# battery_monitor_6803-2_Rev5.net
KiCad netlist of a schematic drawn in EAGLE
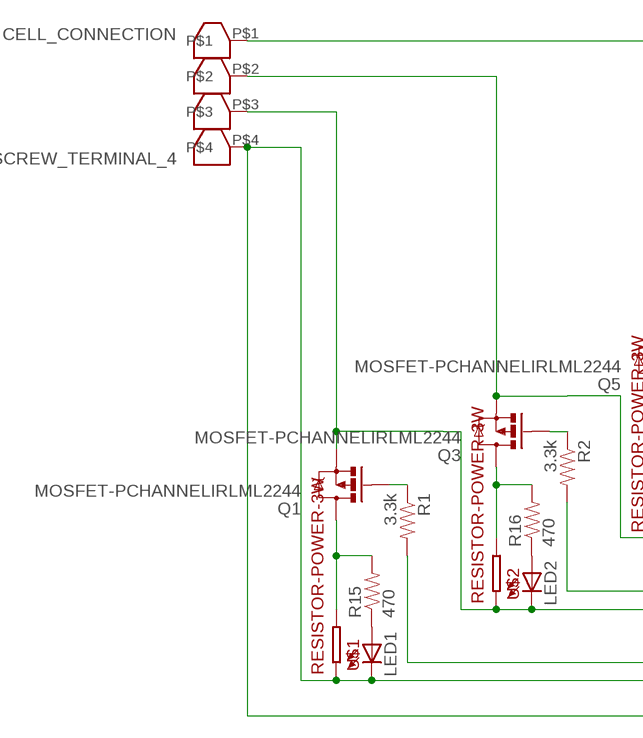
[diagram p0: schematic, sheet 1, part 1 of 2]
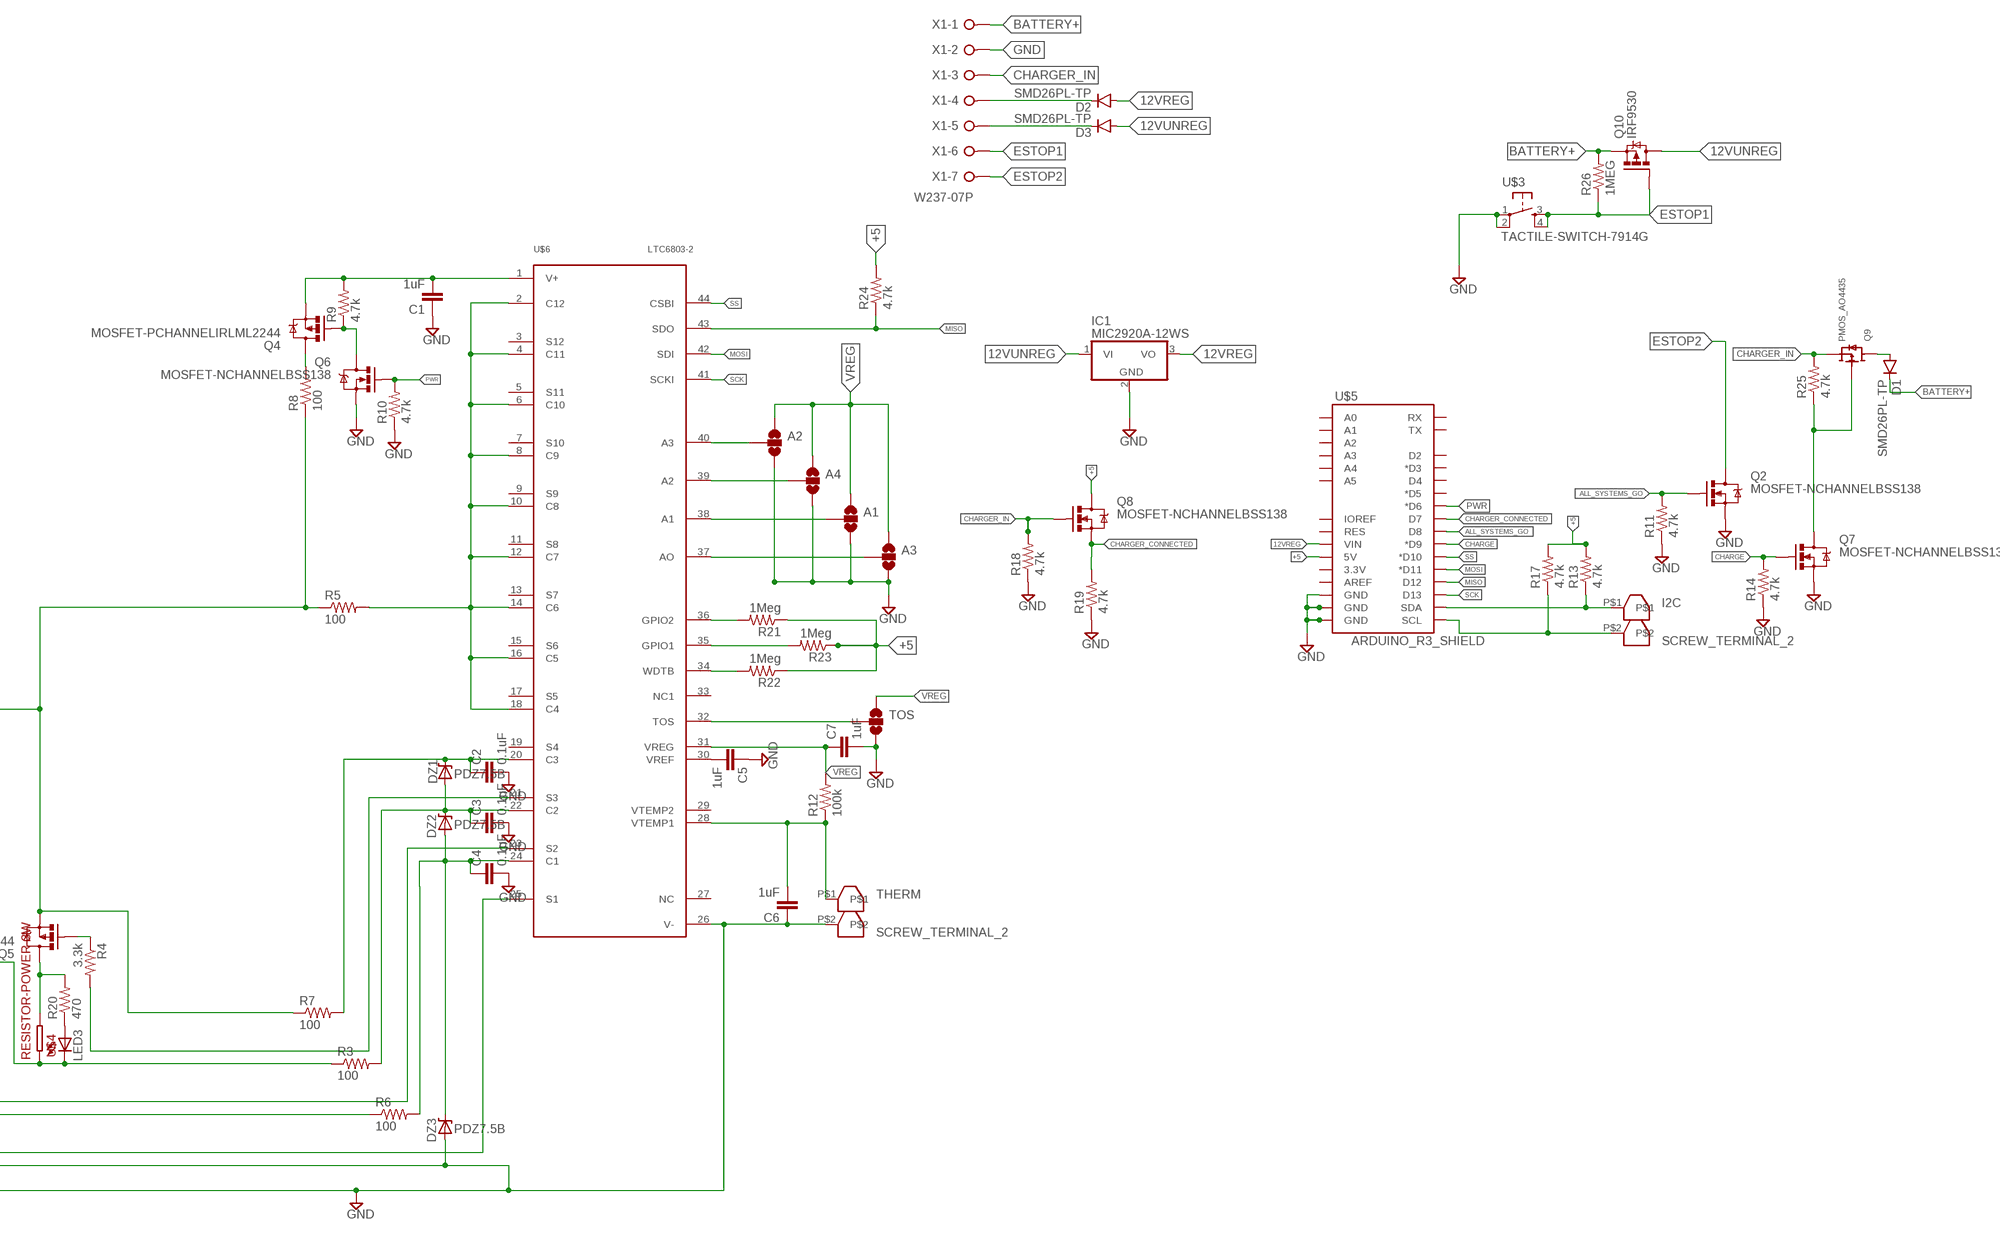
[diagram p1: schematic, sheet 1, part 2 of 2]

(export (version "E")
  (design (tool "Eeschema 10.0.6"))
  (components
    (comp (ref "A1")
      (value "SOLDERJUMPER_2WAYS")
      (footprint "eagle-import:SJ_3")
      (libsource (lib "eagle-import") (part "SOLDERJUMPER_2WAYS"))
    )
    (comp (ref "A2")
      (value "SOLDERJUMPER_2WAYS")
      (footprint "eagle-import:SJ_3")
      (libsource (lib "eagle-import") (part "SOLDERJUMPER_2WAYS"))
    )
    (comp (ref "A3")
      (value "SOLDERJUMPER_2WAYS")
      (footprint "eagle-import:SJ_3")
      (libsource (lib "eagle-import") (part "SOLDERJUMPER_2WAYS"))
    )
    (comp (ref "A4")
      (value "SOLDERJUMPER_2WAYS")
      (footprint "eagle-import:SJ_3")
      (libsource (lib "eagle-import") (part "SOLDERJUMPER_2WAYS"))
    )
    (comp (ref "C1")
      (value "1uF")
      (footprint "eagle-import:0603-CAP")
      (fields (field (name "MPN") "C0603X5R0J105M030BC") (field (name "PROD_ID") "CAP-08390"))
      (libsource (lib "eagle-import") (part "0.1UF-100V-10%(0603)"))
    )
    (comp (ref "C2")
      (value "0.1uF")
      (footprint "eagle-import:0603-CAP")
      (fields (field (name "MF") "AVX CORPORATION") (field (name "MPN") "0603YG104ZAT2A"))
      (libsource (lib "eagle-import") (part "0.1UF-100V-10%(0603)"))
    )
    (comp (ref "C3")
      (value "0.1uF")
      (footprint "eagle-import:0603-CAP")
      (fields (field (name "MF") "AVX CORPORATION") (field (name "MPN") "0603YG104ZAT2A"))
      (libsource (lib "eagle-import") (part "0.1UF-100V-10%(0603)"))
    )
    (comp (ref "C4")
      (value "0.1uF")
      (footprint "eagle-import:0603-CAP")
      (fields (field (name "MF") "AVX CORPORATION") (field (name "MPN") "0603YG104ZAT2A"))
      (libsource (lib "eagle-import") (part "0.1UF-100V-10%(0603)"))
    )
    (comp (ref "C5")
      (value "1uF")
      (footprint "eagle-import:0603-CAP")
      (fields (field (name "MPN") "C0603X5R0J105M030BC") (field (name "PROD_ID") "CAP-08390"))
      (libsource (lib "eagle-import") (part "0.1UF-100V-10%(0603)"))
    )
    (comp (ref "C6")
      (value "1uF")
      (footprint "eagle-import:0603-CAP")
      (fields (field (name "MPN") "C0603X5R0J105M030BC") (field (name "PROD_ID") "CAP-08390"))
      (libsource (lib "eagle-import") (part "0.1UF-100V-10%(0603)"))
    )
    (comp (ref "C7")
      (value "1uF")
      (footprint "eagle-import:0603-CAP")
      (fields (field (name "MPN") "C0603X5R0J105M030BC") (field (name "PROD_ID") "CAP-08390"))
      (libsource (lib "eagle-import") (part "0.1UF-100V-10%(0603)"))
    )
    (comp (ref "CELL_CONNECTION")
      (value "SCREW_TERMINAL_4")
      (footprint "eagle-import:SCREW_TERMINAL_4")
      (fields (field (name "MF") "TYCO ELECTRONICS") (field (name "MPN") "282834-4"))
      (libsource (lib "eagle-import") (part "SCREW_TERMINAL_4"))
    )
    (comp (ref "D1")
      (value "SMD26PL-TP")
      (footprint "eagle-import:SOD-123")
      (libsource (lib "eagle-import") (part "DIODESOD123"))
    )
    (comp (ref "D2")
      (value "SMD26PL-TP")
      (footprint "eagle-import:SOD-123")
      (libsource (lib "eagle-import") (part "DIODESOD123"))
    )
    (comp (ref "D3")
      (value "SMD26PL-TP")
      (footprint "eagle-import:SOD-123")
      (libsource (lib "eagle-import") (part "DIODESOD123"))
    )
    (comp (ref "DZ1")
      (value "PDZ7.5B")
      (footprint "eagle-import:SOD-323@1")
      (fields (field (name "MPN") "PDZ7.5B,115"))
      (libsource (lib "eagle-import") (part "DIODE-ZENER-BZT52"))
    )
    (comp (ref "DZ2")
      (value "PDZ7.5B")
      (footprint "eagle-import:SOD-323@1")
      (fields (field (name "MPN") "PDZ7.5B,115"))
      (libsource (lib "eagle-import") (part "DIODE-ZENER-BZT52"))
    )
    (comp (ref "DZ3")
      (value "PDZ7.5B")
      (footprint "eagle-import:SOD-323@1")
      (fields (field (name "MPN") "PDZ7.5B,115"))
      (libsource (lib "eagle-import") (part "DIODE-ZENER-BZT52"))
    )
    (comp (ref "I2C")
      (value "SCREW_TERMINAL_2")
      (footprint "eagle-import:SCREW_TERMINAL_2")
      (fields (field (name "MF") "TYCO ELECTRONICS") (field (name "MPN") "282834-2"))
      (libsource (lib "eagle-import") (part "SCREW_TERMINAL_2"))
    )
    (comp (ref "IC1")
      (value "MIC2920A-12WS")
      (footprint "eagle-import:SOT223")
      (libsource (lib "eagle-import") (part "MCP1703DB"))
    )
    (comp (ref "LED1")
      (value "LED0603")
      (footprint "eagle-import:LED-0603")
      (fields (field (name "MPN") "150060RS75000"))
      (libsource (lib "eagle-import") (part "LED0603"))
    )
    (comp (ref "LED2")
      (value "LED0603")
      (footprint "eagle-import:LED-0603")
      (fields (field (name "MPN") "150060RS75000"))
      (libsource (lib "eagle-import") (part "LED0603"))
    )
    (comp (ref "LED3")
      (value "LED0603")
      (footprint "eagle-import:LED-0603")
      (fields (field (name "MPN") "150060RS75000"))
      (libsource (lib "eagle-import") (part "LED0603"))
    )
    (comp (ref "Q1")
      (value "MOSFET-PCHANNELIRLML2244")
      (footprint "eagle-import:SOT23-3@1")
      (fields (field (name "MPN") "SI2369DS-T1-GE3"))
      (libsource (lib "eagle-import") (part "MOSFET-PCHANNELIRLML2244"))
    )
    (comp (ref "Q2")
      (value "MOSFET-NCHANNELBSS138")
      (footprint "eagle-import:SOT23")
      (fields (field (name "MPN") "IRLML0030TRPBF"))
      (libsource (lib "eagle-import") (part "MOSFET-NCHANNELBSS138"))
    )
    (comp (ref "Q3")
      (value "MOSFET-PCHANNELIRLML2244")
      (footprint "eagle-import:SOT23-3@1")
      (fields (field (name "MPN") "SI2369DS-T1-GE3"))
      (libsource (lib "eagle-import") (part "MOSFET-PCHANNELIRLML2244"))
    )
    (comp (ref "Q4")
      (value "MOSFET-PCHANNELIRLML2244")
      (footprint "eagle-import:SOT23-3@1")
      (fields (field (name "MPN") "SI2369DS-T1-GE3"))
      (libsource (lib "eagle-import") (part "MOSFET-PCHANNELIRLML2244"))
    )
    (comp (ref "Q5")
      (value "MOSFET-PCHANNELIRLML2244")
      (footprint "eagle-import:SOT23-3@1")
      (fields (field (name "MPN") "SI2369DS-T1-GE3"))
      (libsource (lib "eagle-import") (part "MOSFET-PCHANNELIRLML2244"))
    )
    (comp (ref "Q6")
      (value "MOSFET-NCHANNELBSS138")
      (footprint "eagle-import:SOT23")
      (fields (field (name "MPN") "IRLML0030TRPBF"))
      (libsource (lib "eagle-import") (part "MOSFET-NCHANNELBSS138"))
    )
    (comp (ref "Q7")
      (value "MOSFET-NCHANNELBSS138")
      (footprint "eagle-import:SOT23")
      (fields (field (name "MPN") "IRLML0030TRPBF"))
      (libsource (lib "eagle-import") (part "MOSFET-NCHANNELBSS138"))
    )
    (comp (ref "Q8")
      (value "MOSFET-NCHANNELBSS138")
      (footprint "eagle-import:SOT23")
      (fields (field (name "MPN") "IRLML0030TRPBF") (field (name "PROD_ID") "TRANS-00830"))
      (libsource (lib "eagle-import") (part "MOSFET-NCHANNELBSS138"))
    )
    (comp (ref "Q9")
      (value "PMOS_AO4435")
      (footprint "eagle-import:SOIC8")
      (fields (field (name "MPN") "SI9407BDY-T1-GE3"))
      (libsource (lib "eagle-import") (part "PMOS_AO4435"))
    )
    (comp (ref "Q10")
      (value "IRF9530")
      (footprint "eagle-import:TO220BV")
      (fields (field (name "MPN") "NTE2383"))
      (libsource (lib "eagle-import") (part "IRF9530"))
    )
    (comp (ref "R1")
      (value "3.3k")
      (footprint "eagle-import:0603-RES")
      (fields (field (name "MF") "VISHAY/DALE") (field (name "MPN") "CRCW06033K00FKEA"))
      (libsource (lib "eagle-import") (part "3.3KOHM1/10W1%(0603)"))
    )
    (comp (ref "R2")
      (value "3.3k")
      (footprint "eagle-import:0603-RES")
      (fields (field (name "MF") "VISHAY/DALE") (field (name "MPN") "CRCW06033K00FKEA"))
      (libsource (lib "eagle-import") (part "3.3KOHM1/10W1%(0603)"))
    )
    (comp (ref "R3")
      (value "100")
      (footprint "eagle-import:0603-RES")
      (fields (field (name "MPN") "ERJ-1GNF1000C"))
      (libsource (lib "eagle-import") (part "3.3KOHM1/10W1%(0603)"))
    )
    (comp (ref "R4")
      (value "3.3k")
      (footprint "eagle-import:0603-RES")
      (fields (field (name "MF") "VISHAY/DALE") (field (name "MPN") "CRCW06033K00FKEA"))
      (libsource (lib "eagle-import") (part "3.3KOHM1/10W1%(0603)"))
    )
    (comp (ref "R5")
      (value "100")
      (footprint "eagle-import:0603-RES")
      (fields (field (name "MPN") "ERJ-1GNF1000C"))
      (libsource (lib "eagle-import") (part "3.3KOHM1/10W1%(0603)"))
    )
    (comp (ref "R6")
      (value "100")
      (footprint "eagle-import:0603-RES")
      (fields (field (name "MPN") "ERJ-1GNF1000C"))
      (libsource (lib "eagle-import") (part "3.3KOHM1/10W1%(0603)"))
    )
    (comp (ref "R7")
      (value "100")
      (footprint "eagle-import:0603-RES")
      (fields (field (name "MPN") "ERJ-1GNF1000C"))
      (libsource (lib "eagle-import") (part "3.3KOHM1/10W1%(0603)"))
    )
    (comp (ref "R8")
      (value "100")
      (footprint "eagle-import:0603-RES")
      (fields (field (name "MPN") "ERJ-1GNF1000C"))
      (libsource (lib "eagle-import") (part "3.3KOHM1/10W1%(0603)"))
    )
    (comp (ref "R9")
      (value "4.7k")
      (footprint "eagle-import:0603-RES")
      (fields (field (name "MF") "VISHAY/DALE") (field (name "MPN") "CRCW06034K70FKEA"))
      (libsource (lib "eagle-import") (part "3.3KOHM1/10W1%(0603)"))
    )
    (comp (ref "R10")
      (value "4.7k")
      (footprint "eagle-import:0603-RES")
      (fields (field (name "MF") "VISHAY/DALE") (field (name "MPN") "CRCW06034K70FKEA"))
      (libsource (lib "eagle-import") (part "3.3KOHM1/10W1%(0603)"))
    )
    (comp (ref "R11")
      (value "4.7k")
      (footprint "eagle-import:0603-RES")
      (fields (field (name "MF") "VISHAY/DALE") (field (name "MPN") "CRCW06034K70FKEA"))
      (libsource (lib "eagle-import") (part "3.3KOHM1/10W1%(0603)"))
    )
    (comp (ref "R12")
      (value "100k")
      (footprint "eagle-import:0603-RES")
      (fields (field (name "MF") "FARNELL") (field (name "MPN") "MC0063W06035100K"))
      (libsource (lib "eagle-import") (part "3.3KOHM1/10W1%(0603)"))
    )
    (comp (ref "R13")
      (value "4.7k")
      (footprint "eagle-import:0603-RES")
      (fields (field (name "MF") "VISHAY/DALE") (field (name "MPN") "CRCW06034K70FKEA"))
      (libsource (lib "eagle-import") (part "3.3KOHM1/10W1%(0603)"))
    )
    (comp (ref "R14")
      (value "4.7k")
      (footprint "eagle-import:0603-RES")
      (fields (field (name "MF") "VISHAY/DALE") (field (name "MPN") "CRCW06034K70FKEA"))
      (libsource (lib "eagle-import") (part "3.3KOHM1/10W1%(0603)"))
    )
    (comp (ref "R15")
      (value "470")
      (footprint "eagle-import:0603-RES")
      (fields (field (name "MPN") "ERJ-P03F4700V") (field (name "PROD_ID") "RES-07851"))
      (libsource (lib "eagle-import") (part "3.3KOHM1/10W1%(0603)"))
    )
    (comp (ref "R16")
      (value "470")
      (footprint "eagle-import:0603-RES")
      (fields (field (name "MPN") "ERJ-P03F4700V") (field (name "PROD_ID") "RES-07851"))
      (libsource (lib "eagle-import") (part "3.3KOHM1/10W1%(0603)"))
    )
    (comp (ref "R17")
      (value "4.7k")
      (footprint "eagle-import:0603-RES")
      (fields (field (name "MF") "VISHAY/DALE") (field (name "MPN") "CRCW06034K70FKEA"))
      (libsource (lib "eagle-import") (part "3.3KOHM1/10W1%(0603)"))
    )
    (comp (ref "R18")
      (value "4.7k")
      (footprint "eagle-import:0603-RES")
      (fields
        (field (name "MF") "VISHAY/DALE")
        (field (name "MPN") "CRCW06034K70FKEA")
        (field (name "PROD_ID") "RES-07851")
      )
      (libsource (lib "eagle-import") (part "3.3KOHM1/10W1%(0603)"))
    )
    (comp (ref "R19")
      (value "4.7k")
      (footprint "eagle-import:0603-RES")
      (fields
        (field (name "MF") "VISHAY/DALE")
        (field (name "MPN") "CRCW06034K70FKEA")
        (field (name "PROD_ID") "RES-07851")
      )
      (libsource (lib "eagle-import") (part "3.3KOHM1/10W1%(0603)"))
    )
    (comp (ref "R20")
      (value "470")
      (footprint "eagle-import:0603-RES")
      (fields (field (name "MPN") "ERJ-P03F4700V") (field (name "PROD_ID") "RES-07851"))
      (libsource (lib "eagle-import") (part "3.3KOHM1/10W1%(0603)"))
    )
    (comp (ref "R21")
      (value "1Meg")
      (footprint "eagle-import:0603-RES")
      (fields (field (name "MPN") "ERJ-3EKF1004V") (field (name "PROD_ID") "RES-07851"))
      (libsource (lib "eagle-import") (part "3.3KOHM1/10W1%(0603)"))
    )
    (comp (ref "R22")
      (value "1Meg")
      (footprint "eagle-import:0603-RES")
      (fields (field (name "MPN") "ERJ-3EKF1004V") (field (name "PROD_ID") "RES-07851"))
      (libsource (lib "eagle-import") (part "3.3KOHM1/10W1%(0603)"))
    )
    (comp (ref "R23")
      (value "1Meg")
      (footprint "eagle-import:0603-RES")
      (fields (field (name "MPN") "ERJ-3EKF1004V") (field (name "PROD_ID") "RES-07851"))
      (libsource (lib "eagle-import") (part "3.3KOHM1/10W1%(0603)"))
    )
    (comp (ref "R24")
      (value "4.7k")
      (footprint "eagle-import:0603-RES")
      (fields
        (field (name "MF") "VISHAY/DALE")
        (field (name "MPN") "CRCW06034K70FKEA")
        (field (name "PROD_ID") "RES-07851")
      )
      (libsource (lib "eagle-import") (part "3.3KOHM1/10W1%(0603)"))
    )
    (comp (ref "R25")
      (value "4.7k")
      (footprint "eagle-import:0603-RES")
      (fields
        (field (name "MF") "VISHAY/DALE")
        (field (name "MPN") "CRCW06034K70FKEA")
        (field (name "PROD_ID") "RES-07851")
      )
      (libsource (lib "eagle-import") (part "3.3KOHM1/10W1%(0603)"))
    )
    (comp (ref "R26")
      (value "1MEG")
      (footprint "eagle-import:0603-RES")
      (fields (field (name "MPN") "ERJ-3EKF1004V"))
      (libsource (lib "eagle-import") (part "3.3KOHM1/10W1%(0603)"))
    )
    (comp (ref "THERM")
      (value "SCREW_TERMINAL_2")
      (footprint "eagle-import:SCREW_TERMINAL_2")
      (fields (field (name "MF") "TYCO ELECTRONICS") (field (name "MPN") "282834-2"))
      (libsource (lib "eagle-import") (part "SCREW_TERMINAL_2"))
    )
    (comp (ref "TOS")
      (value "SOLDERJUMPER_2WAYS")
      (footprint "eagle-import:SJ_3")
      (libsource (lib "eagle-import") (part "SOLDERJUMPER_2WAYS"))
    )
    (comp (ref "U$1")
      (value "RESISTOR-POWER-3W")
      (footprint "eagle-import:RESISTOR-3W")
      (fields (field (name "MPN") "ERG-3SJ200"))
      (libsource (lib "eagle-import") (part "RESISTOR-POWER-3W"))
    )
    (comp (ref "U$2")
      (value "RESISTOR-POWER-3W")
      (footprint "eagle-import:RESISTOR-3W")
      (fields (field (name "MPN") "ERG-3SJ200"))
      (libsource (lib "eagle-import") (part "RESISTOR-POWER-3W"))
    )
    (comp (ref "U$3")
      (value "TACTILE-SWITCH-7914G")
      (footprint "eagle-import:7914G")
      (fields (field (name "MF") "BOURNS, INC.") (field (name "MPN") "7914G-1-000E"))
      (libsource (lib "eagle-import") (part "TACTILE-SWITCH-7914G"))
    )
    (comp (ref "U$4")
      (value "RESISTOR-POWER-3W")
      (footprint "eagle-import:RESISTOR-3W")
      (fields (field (name "MPN") "ERG-3SJ200"))
      (libsource (lib "eagle-import") (part "RESISTOR-POWER-3W"))
    )
    (comp (ref "U$5")
      (value "ARDUINO_R3_SHIELD")
      (footprint "eagle-import:UNO_R3_SHIELD")
      (libsource (lib "eagle-import") (part "ARDUINO_R3_SHIELD"))
    )
    (comp (ref "U$6")
      (value "LTC6803-2")
      (footprint "eagle-import:FSOP-44")
      (libsource (lib "eagle-import") (part "LTC6803-2"))
    )
    (comp (ref "X1")
      (value "W237-07P")
      (footprint "eagle-import:W237-7P")
      (libsource (lib "eagle-import") (part "W237-07P"))
    )
  )
  (nets
    (net (code "1") (name "+5") (class "Default")
      (node (ref "Q8") (pin "3") (pinfunction "D_3") (pintype "passive"))
      (node (ref "R13") (pin "2") (pinfunction "2_2") (pintype "passive"))
      (node (ref "R17") (pin "2") (pinfunction "2_2") (pintype "passive"))
      (node (ref "R21") (pin "1") (pinfunction "1_1") (pintype "passive"))
      (node (ref "R22") (pin "1") (pinfunction "1_1") (pintype "passive"))
      (node (ref "R23") (pin "1") (pinfunction "1_1") (pintype "passive"))
      (node (ref "R24") (pin "2") (pinfunction "2_2") (pintype "passive"))
      (node (ref "U$5") (pin "5V") (pinfunction "5V_5V") (pintype "bidirectional"))
    )
    (net (code "2") (name "12VREG") (class "Default")
      (node (ref "D2") (pin "A") (pinfunction "A_A") (pintype "passive"))
      (node (ref "IC1") (pin "3") (pinfunction "VO_3") (pintype "passive"))
      (node (ref "U$5") (pin "VIN") (pinfunction "VIN_VIN") (pintype "bidirectional"))
    )
    (net (code "3") (name "12VUNREG") (class "Default")
      (node (ref "D3") (pin "A") (pinfunction "A_A") (pintype "passive"))
      (node (ref "IC1") (pin "1") (pinfunction "VI_1") (pintype "input"))
      (node (ref "Q10") (pin "D") (pinfunction "D_D") (pintype "passive"))
    )
    (net (code "4") (name "ALL_SYSTEMS_GO") (class "Default")
      (node (ref "Q2") (pin "1") (pinfunction "G_1") (pintype "passive"))
      (node (ref "R11") (pin "2") (pinfunction "2_2") (pintype "passive"))
      (node (ref "U$5") (pin "D8") (pinfunction "D8_D8") (pintype "bidirectional"))
    )
    (net (code "5") (name "BATTERY+") (class "Default")
      (node (ref "D1") (pin "C") (pinfunction "C_C") (pintype "passive"))
      (node (ref "Q10") (pin "S") (pinfunction "S_S") (pintype "passive"))
      (node (ref "R26") (pin "2") (pinfunction "2_2") (pintype "passive"))
      (node (ref "X1") (pin "1") (pinfunction "KL_1") (pintype "passive"))
    )
    (net (code "6") (name "CHARGE") (class "Default")
      (node (ref "Q7") (pin "1") (pinfunction "G_1") (pintype "passive"))
      (node (ref "R14") (pin "2") (pinfunction "2_2") (pintype "passive"))
      (node (ref "U$5") (pin "D9") (pinfunction "*D9_D9") (pintype "bidirectional"))
    )
    (net (code "7") (name "CHARGER_CONNECTED") (class "Default")
      (node (ref "Q8") (pin "2") (pinfunction "S_2") (pintype "passive"))
      (node (ref "R19") (pin "2") (pinfunction "2_2") (pintype "passive"))
      (node (ref "U$5") (pin "D7") (pinfunction "D7_D7") (pintype "bidirectional"))
    )
    (net (code "8") (name "CHARGER_IN") (class "Default")
      (node (ref "Q8") (pin "1") (pinfunction "G_1") (pintype "passive"))
      (node (ref "Q9") (pin "1") (pinfunction "SOURCE_1") (pintype "bidirectional"))
      (node (ref "Q9") (pin "2") (pinfunction "SOURCE_2") (pintype "bidirectional"))
      (node (ref "Q9") (pin "3") (pinfunction "SOURCE_3") (pintype "bidirectional"))
      (node (ref "R18") (pin "2") (pinfunction "2_2") (pintype "passive"))
      (node (ref "R25") (pin "2") (pinfunction "2_2") (pintype "passive"))
      (node (ref "X1") (pin "3") (pinfunction "KL_3") (pintype "passive"))
    )
    (net (code "9") (name "ESTOP1") (class "Default")
      (node (ref "Q10") (pin "G") (pinfunction "G_G") (pintype "passive"))
      (node (ref "R26") (pin "1") (pinfunction "1_1") (pintype "passive"))
      (node (ref "U$3") (pin "3") (pinfunction "3_3") (pintype "passive"))
      (node (ref "U$3") (pin "4") (pinfunction "4_4") (pintype "passive"))
      (node (ref "X1") (pin "6") (pinfunction "KL_6") (pintype "passive"))
    )
    (net (code "10") (name "ESTOP2") (class "Default")
      (node (ref "Q2") (pin "3") (pinfunction "D_3") (pintype "passive"))
      (node (ref "X1") (pin "7") (pinfunction "KL_7") (pintype "passive"))
    )
    (net (code "11") (name "GND") (class "Default")
      (node (ref "A1") (pin "3") (pinfunction "3_3") (pintype "passive"))
      (node (ref "A2") (pin "3") (pinfunction "3_3") (pintype "passive"))
      (node (ref "A3") (pin "3") (pinfunction "3_3") (pintype "passive"))
      (node (ref "A4") (pin "3") (pinfunction "3_3") (pintype "passive"))
      (node (ref "C1") (pin "1") (pinfunction "1_1") (pintype "passive"))
      (node (ref "C2") (pin "2") (pinfunction "2_2") (pintype "passive"))
      (node (ref "C3") (pin "2") (pinfunction "2_2") (pintype "passive"))
      (node (ref "C4") (pin "2") (pinfunction "2_2") (pintype "passive"))
      (node (ref "C5") (pin "1") (pinfunction "1_1") (pintype "passive"))
      (node (ref "C6") (pin "1") (pinfunction "1_1") (pintype "passive"))
      (node (ref "C7") (pin "2") (pinfunction "2_2") (pintype "passive"))
      (node (ref "CELL_CONNECTION") (pin "P$4") (pinfunction "P$4_P$4") (pintype "bidirectional"))
      (node (ref "DZ3") (pin "2") (pinfunction "A_2") (pintype "passive"))
      (node (ref "IC1") (pin "2") (pinfunction "GND_2") (pintype "passive"))
      (node (ref "LED1") (pin "C") (pinfunction "C_C") (pintype "passive"))
      (node (ref "Q2") (pin "2") (pinfunction "S_2") (pintype "passive"))
      (node (ref "Q6") (pin "2") (pinfunction "S_2") (pintype "passive"))
      (node (ref "Q7") (pin "2") (pinfunction "S_2") (pintype "passive"))
      (node (ref "R10") (pin "1") (pinfunction "1_1") (pintype "passive"))
      (node (ref "R11") (pin "1") (pinfunction "1_1") (pintype "passive"))
      (node (ref "R14") (pin "1") (pinfunction "1_1") (pintype "passive"))
      (node (ref "R18") (pin "1") (pinfunction "1_1") (pintype "passive"))
      (node (ref "R19") (pin "1") (pinfunction "1_1") (pintype "passive"))
      (node (ref "THERM") (pin "P$2") (pinfunction "P$2_P$2") (pintype "bidirectional"))
      (node (ref "TOS") (pin "3") (pinfunction "3_3") (pintype "passive"))
      (node (ref "U$1") (pin "P$2") (pinfunction "P$2_P$2") (pintype "bidirectional"))
      (node (ref "U$3") (pin "1") (pinfunction "1_1") (pintype "passive"))
      (node (ref "U$3") (pin "2") (pinfunction "2_2") (pintype "passive"))
      (node (ref "U$5") (pin "GND@0") (pinfunction "GND_GND@0") (pintype "bidirectional"))
      (node (ref "U$5") (pin "GND@1") (pinfunction "GND_GND@1") (pintype "bidirectional"))
      (node (ref "U$5") (pin "GND@2") (pinfunction "GND_GND@2") (pintype "bidirectional"))
      (node (ref "U$6") (pin "26") (pinfunction "V-_26") (pintype "bidirectional"))
      (node (ref "X1") (pin "2") (pinfunction "KL_2") (pintype "passive"))
    )
    (net (code "12") (name "MISO") (class "Default")
      (node (ref "R24") (pin "1") (pinfunction "1_1") (pintype "passive"))
      (node (ref "U$5") (pin "D12") (pinfunction "D12_D12") (pintype "bidirectional"))
      (node (ref "U$6") (pin "43") (pinfunction "SDO_43") (pintype "bidirectional"))
    )
    (net (code "13") (name "MOSI") (class "Default")
      (node (ref "U$5") (pin "D11") (pinfunction "*D11_D11") (pintype "bidirectional"))
      (node (ref "U$6") (pin "42") (pinfunction "SDI_42") (pintype "bidirectional"))
    )
    (net (code "14") (name "Net-(D1-PadA)") (class "Default")
      (node (ref "D1") (pin "A") (pinfunction "A_A") (pintype "passive"))
      (node (ref "Q9") (pin "5") (pinfunction "DRAIN_5") (pintype "bidirectional"))
      (node (ref "Q9") (pin "6") (pinfunction "DRAIN_6") (pintype "bidirectional"))
      (node (ref "Q9") (pin "7") (pinfunction "DRAIN_7") (pintype "bidirectional"))
      (node (ref "Q9") (pin "8") (pinfunction "DRAIN_8") (pintype "bidirectional"))
    )
    (net (code "15") (name "Net-(DZ1-A)") (class "Default")
      (node (ref "C3") (pin "1") (pinfunction "1_1") (pintype "passive"))
      (node (ref "DZ1") (pin "2") (pinfunction "A_2") (pintype "passive"))
      (node (ref "DZ2") (pin "1") (pinfunction "C_1") (pintype "passive"))
      (node (ref "R3") (pin "2") (pinfunction "2_2") (pintype "passive"))
      (node (ref "U$6") (pin "22") (pinfunction "C2_22") (pintype "bidirectional"))
    )
    (net (code "16") (name "Net-(DZ1-C)") (class "Default")
      (node (ref "C2") (pin "1") (pinfunction "1_1") (pintype "passive"))
      (node (ref "DZ1") (pin "1") (pinfunction "C_1") (pintype "passive"))
      (node (ref "R7") (pin "2") (pinfunction "2_2") (pintype "passive"))
      (node (ref "U$6") (pin "20") (pinfunction "C3_20") (pintype "bidirectional"))
    )
    (net (code "17") (name "Net-(DZ2-A)") (class "Default")
      (node (ref "C4") (pin "1") (pinfunction "1_1") (pintype "passive"))
      (node (ref "DZ2") (pin "2") (pinfunction "A_2") (pintype "passive"))
      (node (ref "DZ3") (pin "1") (pinfunction "C_1") (pintype "passive"))
      (node (ref "R6") (pin "2") (pinfunction "2_2") (pintype "passive"))
      (node (ref "U$6") (pin "24") (pinfunction "C1_24") (pintype "bidirectional"))
    )
    (net (code "18") (name "Net-(I2C-PadP$1)") (class "Default")
      (node (ref "I2C") (pin "P$1") (pinfunction "P$1_P$1") (pintype "bidirectional"))
      (node (ref "R13") (pin "1") (pinfunction "1_1") (pintype "passive"))
      (node (ref "U$5") (pin "SDA") (pinfunction "SDA_SDA") (pintype "bidirectional"))
    )
    (net (code "19") (name "Net-(I2C-PadP$2)") (class "Default")
      (node (ref "I2C") (pin "P$2") (pinfunction "P$2_P$2") (pintype "bidirectional"))
      (node (ref "R17") (pin "1") (pinfunction "1_1") (pintype "passive"))
      (node (ref "U$5") (pin "SCL") (pinfunction "SCL_SCL") (pintype "bidirectional"))
    )
    (net (code "20") (name "Net-(LED1-PadA)") (class "Default")
      (node (ref "LED1") (pin "A") (pinfunction "A_A") (pintype "passive"))
      (node (ref "R15") (pin "1") (pinfunction "1_1") (pintype "passive"))
    )
    (net (code "21") (name "Net-(LED2-PadA)") (class "Default")
      (node (ref "LED2") (pin "A") (pinfunction "A_A") (pintype "passive"))
      (node (ref "R16") (pin "1") (pinfunction "1_1") (pintype "passive"))
    )
    (net (code "22") (name "Net-(LED3-PadA)") (class "Default")
      (node (ref "LED3") (pin "A") (pinfunction "A_A") (pintype "passive"))
      (node (ref "R20") (pin "1") (pinfunction "1_1") (pintype "passive"))
    )
    (net (code "23") (name "Net-(Q1-D)") (class "Default")
      (node (ref "Q1") (pin "3") (pinfunction "D_3") (pintype "passive"))
      (node (ref "R15") (pin "2") (pinfunction "2_2") (pintype "passive"))
      (node (ref "U$1") (pin "P$1") (pinfunction "P$1_P$1") (pintype "bidirectional"))
    )
    (net (code "24") (name "Net-(Q1-G)") (class "Default")
      (node (ref "Q1") (pin "1") (pinfunction "G_1") (pintype "passive"))
      (node (ref "R1") (pin "1") (pinfunction "1_1") (pintype "passive"))
    )
    (net (code "25") (name "Net-(Q1-S)") (class "Default")
      (node (ref "CELL_CONNECTION") (pin "P$3") (pinfunction "P$3_P$3") (pintype "bidirectional"))
      (node (ref "LED2") (pin "C") (pinfunction "C_C") (pintype "passive"))
      (node (ref "Q1") (pin "2") (pinfunction "S_2") (pintype "passive"))
      (node (ref "R6") (pin "1") (pinfunction "1_1") (pintype "passive"))
      (node (ref "U$2") (pin "P$2") (pinfunction "P$2_P$2") (pintype "bidirectional"))
    )
    (net (code "26") (name "Net-(Q3-D)") (class "Default")
      (node (ref "Q3") (pin "3") (pinfunction "D_3") (pintype "passive"))
      (node (ref "R16") (pin "2") (pinfunction "2_2") (pintype "passive"))
      (node (ref "U$2") (pin "P$1") (pinfunction "P$1_P$1") (pintype "bidirectional"))
    )
    (net (code "27") (name "Net-(Q3-G)") (class "Default")
      (node (ref "Q3") (pin "1") (pinfunction "G_1") (pintype "passive"))
      (node (ref "R2") (pin "1") (pinfunction "1_1") (pintype "passive"))
    )
    (net (code "28") (name "Net-(Q3-S)") (class "Default")
      (node (ref "CELL_CONNECTION") (pin "P$2") (pinfunction "P$2_P$2") (pintype "bidirectional"))
      (node (ref "LED3") (pin "C") (pinfunction "C_C") (pintype "passive"))
      (node (ref "Q3") (pin "2") (pinfunction "S_2") (pintype "passive"))
      (node (ref "R3") (pin "1") (pinfunction "1_1") (pintype "passive"))
      (node (ref "U$4") (pin "P$2") (pinfunction "P$2_P$2") (pintype "bidirectional"))
    )
    (net (code "29") (name "Net-(Q4-D)") (class "Default")
      (node (ref "Q4") (pin "3") (pinfunction "D_3") (pintype "passive"))
      (node (ref "R8") (pin "2") (pinfunction "2_2") (pintype "passive"))
    )
    (net (code "30") (name "Net-(Q4-G)") (class "Default")
      (node (ref "Q4") (pin "1") (pinfunction "G_1") (pintype "passive"))
      (node (ref "Q6") (pin "3") (pinfunction "D_3") (pintype "passive"))
      (node (ref "R9") (pin "1") (pinfunction "1_1") (pintype "passive"))
    )
    (net (code "31") (name "Net-(Q4-S)") (class "Default")
      (node (ref "C1") (pin "2") (pinfunction "2_2") (pintype "passive"))
      (node (ref "Q4") (pin "2") (pinfunction "S_2") (pintype "passive"))
      (node (ref "R9") (pin "2") (pinfunction "2_2") (pintype "passive"))
      (node (ref "U$6") (pin "1") (pinfunction "V+_1") (pintype "bidirectional"))
    )
    (net (code "32") (name "Net-(Q5-D)") (class "Default")
      (node (ref "Q5") (pin "3") (pinfunction "D_3") (pintype "passive"))
      (node (ref "R20") (pin "2") (pinfunction "2_2") (pintype "passive"))
      (node (ref "U$4") (pin "P$1") (pinfunction "P$1_P$1") (pintype "bidirectional"))
    )
    (net (code "33") (name "Net-(Q5-G)") (class "Default")
      (node (ref "Q5") (pin "1") (pinfunction "G_1") (pintype "passive"))
      (node (ref "R4") (pin "1") (pinfunction "1_1") (pintype "passive"))
    )
    (net (code "34") (name "Net-(Q5-S)") (class "Default")
      (node (ref "CELL_CONNECTION") (pin "P$1") (pinfunction "P$1_P$1") (pintype "bidirectional"))
      (node (ref "Q5") (pin "2") (pinfunction "S_2") (pintype "passive"))
      (node (ref "R5") (pin "1") (pinfunction "1_1") (pintype "passive"))
      (node (ref "R7") (pin "1") (pinfunction "1_1") (pintype "passive"))
      (node (ref "R8") (pin "1") (pinfunction "1_1") (pintype "passive"))
    )
    (net (code "35") (name "Net-(Q7-D)") (class "Default")
      (node (ref "Q7") (pin "3") (pinfunction "D_3") (pintype "passive"))
      (node (ref "Q9") (pin "4") (pinfunction "GATE_4") (pintype "bidirectional"))
      (node (ref "R25") (pin "1") (pinfunction "1_1") (pintype "passive"))
    )
    (net (code "36") (name "Net-(U$6-A1)") (class "Default")
      (node (ref "A1") (pin "2") (pinfunction "2_2") (pintype "passive"))
      (node (ref "U$6") (pin "38") (pinfunction "A1_38") (pintype "bidirectional"))
    )
    (net (code "37") (name "Net-(U$6-A2)") (class "Default")
      (node (ref "A4") (pin "2") (pinfunction "2_2") (pintype "passive"))
      (node (ref "U$6") (pin "39") (pinfunction "A2_39") (pintype "bidirectional"))
    )
    (net (code "38") (name "Net-(U$6-A3)") (class "Default")
      (node (ref "A2") (pin "2") (pinfunction "2_2") (pintype "passive"))
      (node (ref "U$6") (pin "40") (pinfunction "A3_40") (pintype "bidirectional"))
    )
    (net (code "39") (name "Net-(U$6-AO)") (class "Default")
      (node (ref "A3") (pin "2") (pinfunction "2_2") (pintype "passive"))
      (node (ref "U$6") (pin "37") (pinfunction "AO_37") (pintype "bidirectional"))
    )
    (net (code "40") (name "Net-(U$6-C10)") (class "Default")
      (node (ref "R5") (pin "2") (pinfunction "2_2") (pintype "passive"))
      (node (ref "U$6") (pin "10") (pinfunction "C8_10") (pintype "bidirectional"))
      (node (ref "U$6") (pin "12") (pinfunction "C7_12") (pintype "bidirectional"))
      (node (ref "U$6") (pin "14") (pinfunction "C6_14") (pintype "bidirectional"))
      (node (ref "U$6") (pin "16") (pinfunction "C5_16") (pintype "bidirectional"))
      (node (ref "U$6") (pin "18") (pinfunction "C4_18") (pintype "bidirectional"))
      (node (ref "U$6") (pin "2") (pinfunction "C12_2") (pintype "bidirectional"))
      (node (ref "U$6") (pin "4") (pinfunction "C11_4") (pintype "bidirectional"))
      (node (ref "U$6") (pin "6") (pinfunction "C10_6") (pintype "bidirectional"))
      (node (ref "U$6") (pin "8") (pinfunction "C9_8") (pintype "bidirectional"))
    )
    (net (code "41") (name "Net-(U$6-GPIO1)") (class "Default")
      (node (ref "R23") (pin "2") (pinfunction "2_2") (pintype "passive"))
      (node (ref "U$6") (pin "35") (pinfunction "GPIO1_35") (pintype "bidirectional"))
    )
    (net (code "42") (name "Net-(U$6-GPIO2)") (class "Default")
      (node (ref "R21") (pin "2") (pinfunction "2_2") (pintype "passive"))
      (node (ref "U$6") (pin "36") (pinfunction "GPIO2_36") (pintype "bidirectional"))
    )
    (net (code "43") (name "Net-(U$6-S1)") (class "Default")
      (node (ref "R1") (pin "2") (pinfunction "2_2") (pintype "passive"))
      (node (ref "U$6") (pin "25") (pinfunction "S1_25") (pintype "bidirectional"))
    )
    (net (code "44") (name "Net-(U$6-S2)") (class "Default")
      (node (ref "R2") (pin "2") (pinfunction "2_2") (pintype "passive"))
      (node (ref "U$6") (pin "23") (pinfunction "S2_23") (pintype "bidirectional"))
    )
    (net (code "45") (name "Net-(U$6-S3)") (class "Default")
      (node (ref "R4") (pin "2") (pinfunction "2_2") (pintype "passive"))
      (node (ref "U$6") (pin "21") (pinfunction "S3_21") (pintype "bidirectional"))
    )
    (net (code "46") (name "Net-(U$6-TOS)") (class "Default")
      (node (ref "TOS") (pin "2") (pinfunction "2_2") (pintype "passive"))
      (node (ref "U$6") (pin "32") (pinfunction "TOS_32") (pintype "bidirectional"))
    )
    (net (code "47") (name "Net-(U$6-VREF)") (class "Default")
      (node (ref "C5") (pin "2") (pinfunction "2_2") (pintype "passive"))
      (node (ref "U$6") (pin "30") (pinfunction "VREF_30") (pintype "bidirectional"))
    )
    (net (code "48") (name "Net-(U$6-VTEMP1)") (class "Default")
      (node (ref "C6") (pin "2") (pinfunction "2_2") (pintype "passive"))
      (node (ref "R12") (pin "1") (pinfunction "1_1") (pintype "passive"))
      (node (ref "THERM") (pin "P$1") (pinfunction "P$1_P$1") (pintype "bidirectional"))
      (node (ref "U$6") (pin "28") (pinfunction "VTEMP1_28") (pintype "bidirectional"))
    )
    (net (code "49") (name "Net-(U$6-WDTB)") (class "Default")
      (node (ref "R22") (pin "2") (pinfunction "2_2") (pintype "passive"))
      (node (ref "U$6") (pin "34") (pinfunction "WDTB_34") (pintype "bidirectional"))
    )
    (net (code "50") (name "Net-(X1D-KL)") (class "Default")
      (node (ref "D2") (pin "C") (pinfunction "C_C") (pintype "passive"))
      (node (ref "X1") (pin "4") (pinfunction "KL_4") (pintype "passive"))
    )
    (net (code "51") (name "Net-(X1E-KL)") (class "Default")
      (node (ref "D3") (pin "C") (pinfunction "C_C") (pintype "passive"))
      (node (ref "X1") (pin "5") (pinfunction "KL_5") (pintype "passive"))
    )
    (net (code "52") (name "PWR") (class "Default")
      (node (ref "Q6") (pin "1") (pinfunction "G_1") (pintype "passive"))
      (node (ref "R10") (pin "2") (pinfunction "2_2") (pintype "passive"))
      (node (ref "U$5") (pin "D6") (pinfunction "*D6_D6") (pintype "bidirectional"))
    )
    (net (code "53") (name "SCK") (class "Default")
      (node (ref "U$5") (pin "D13") (pinfunction "D13_D13") (pintype "bidirectional"))
      (node (ref "U$6") (pin "41") (pinfunction "SCKI_41") (pintype "bidirectional"))
    )
    (net (code "54") (name "SS") (class "Default")
      (node (ref "U$5") (pin "D10") (pinfunction "*D10_D10") (pintype "bidirectional"))
      (node (ref "U$6") (pin "44") (pinfunction "CSBI_44") (pintype "bidirectional"))
    )
    (net (code "55") (name "VREG") (class "Default")
      (node (ref "A1") (pin "1") (pinfunction "1_1") (pintype "passive"))
      (node (ref "A2") (pin "1") (pinfunction "1_1") (pintype "passive"))
      (node (ref "A3") (pin "1") (pinfunction "1_1") (pintype "passive"))
      (node (ref "A4") (pin "1") (pinfunction "1_1") (pintype "passive"))
      (node (ref "C7") (pin "1") (pinfunction "1_1") (pintype "passive"))
      (node (ref "R12") (pin "2") (pinfunction "2_2") (pintype "passive"))
      (node (ref "TOS") (pin "1") (pinfunction "1_1") (pintype "passive"))
      (node (ref "U$6") (pin "31") (pinfunction "VREG_31") (pintype "bidirectional"))
    )
    (net (code "56") (name "unconnected-(U$5-*D3-PadD3)") (class "Default")
      (node (ref "U$5") (pin "D3") (pinfunction "*D3_D3") (pintype "bidirectional"))
    )
    (net (code "57") (name "unconnected-(U$5-*D5-PadD5)") (class "Default")
      (node (ref "U$5") (pin "D5") (pinfunction "*D5_D5") (pintype "bidirectional"))
    )
    (net (code "58") (name "unconnected-(U$5-Pad3.3V)") (class "Default")
      (node (ref "U$5") (pin "3.3V") (pinfunction "3.3V_3.3V") (pintype "bidirectional"))
    )
    (net (code "59") (name "unconnected-(U$5-PadA0)") (class "Default")
      (node (ref "U$5") (pin "A0") (pinfunction "A0_A0") (pintype "bidirectional"))
    )
    (net (code "60") (name "unconnected-(U$5-PadA1)") (class "Default")
      (node (ref "U$5") (pin "A1") (pinfunction "A1_A1") (pintype "bidirectional"))
    )
    (net (code "61") (name "unconnected-(U$5-PadA2)") (class "Default")
      (node (ref "U$5") (pin "A2") (pinfunction "A2_A2") (pintype "bidirectional"))
    )
    (net (code "62") (name "unconnected-(U$5-PadA3)") (class "Default")
      (node (ref "U$5") (pin "A3") (pinfunction "A3_A3") (pintype "bidirectional"))
    )
    (net (code "63") (name "unconnected-(U$5-PadA4)") (class "Default")
      (node (ref "U$5") (pin "A4") (pinfunction "A4_A4") (pintype "bidirectional"))
    )
    (net (code "64") (name "unconnected-(U$5-PadA5)") (class "Default")
      (node (ref "U$5") (pin "A5") (pinfunction "A5_A5") (pintype "bidirectional"))
    )
    (net (code "65") (name "unconnected-(U$5-PadAREF)") (class "Default")
      (node (ref "U$5") (pin "AREF") (pinfunction "AREF_AREF") (pintype "bidirectional"))
    )
    (net (code "66") (name "unconnected-(U$5-PadD2)") (class "Default")
      (node (ref "U$5") (pin "D2") (pinfunction "D2_D2") (pintype "bidirectional"))
    )
    (net (code "67") (name "unconnected-(U$5-PadD4)") (class "Default")
      (node (ref "U$5") (pin "D4") (pinfunction "D4_D4") (pintype "bidirectional"))
    )
    (net (code "68") (name "unconnected-(U$5-PadIOREF)") (class "Default")
      (node (ref "U$5") (pin "IOREF") (pinfunction "IOREF_IOREF") (pintype "bidirectional"))
    )
    (net (code "69") (name "unconnected-(U$5-PadRES)") (class "Default")
      (node (ref "U$5") (pin "RES") (pinfunction "RES_RES") (pintype "bidirectional"))
    )
    (net (code "70") (name "unconnected-(U$5-PadRX)") (class "Default")
      (node (ref "U$5") (pin "RX") (pinfunction "RX_RX") (pintype "bidirectional"))
    )
    (net (code "71") (name "unconnected-(U$5-PadTX)") (class "Default")
      (node (ref "U$5") (pin "TX") (pinfunction "TX_TX") (pintype "bidirectional"))
    )
    (net (code "72") (name "unconnected-(U$6-NC-Pad27)") (class "Default")
      (node (ref "U$6") (pin "27") (pinfunction "NC_27") (pintype "bidirectional"))
    )
    (net (code "73") (name "unconnected-(U$6-NC1-Pad33)") (class "Default")
      (node (ref "U$6") (pin "33") (pinfunction "NC1_33") (pintype "bidirectional"))
    )
    (net (code "74") (name "unconnected-(U$6-S4-Pad19)") (class "Default")
      (node (ref "U$6") (pin "19") (pinfunction "S4_19") (pintype "bidirectional"))
    )
    (net (code "75") (name "unconnected-(U$6-S5-Pad17)") (class "Default")
      (node (ref "U$6") (pin "17") (pinfunction "S5_17") (pintype "bidirectional"))
    )
    (net (code "76") (name "unconnected-(U$6-S6-Pad15)") (class "Default")
      (node (ref "U$6") (pin "15") (pinfunction "S6_15") (pintype "bidirectional"))
    )
    (net (code "77") (name "unconnected-(U$6-S7-Pad13)") (class "Default")
      (node (ref "U$6") (pin "13") (pinfunction "S7_13") (pintype "bidirectional"))
    )
    (net (code "78") (name "unconnected-(U$6-S8-Pad11)") (class "Default")
      (node (ref "U$6") (pin "11") (pinfunction "S8_11") (pintype "bidirectional"))
    )
    (net (code "79") (name "unconnected-(U$6-S9-Pad9)") (class "Default")
      (node (ref "U$6") (pin "9") (pinfunction "S9_9") (pintype "bidirectional"))
    )
    (net (code "80") (name "unconnected-(U$6-S10-Pad7)") (class "Default")
      (node (ref "U$6") (pin "7") (pinfunction "S10_7") (pintype "bidirectional"))
    )
    (net (code "81") (name "unconnected-(U$6-S11-Pad5)") (class "Default")
      (node (ref "U$6") (pin "5") (pinfunction "S11_5") (pintype "bidirectional"))
    )
    (net (code "82") (name "unconnected-(U$6-S12-Pad3)") (class "Default")
      (node (ref "U$6") (pin "3") (pinfunction "S12_3") (pintype "bidirectional"))
    )
    (net (code "83") (name "unconnected-(U$6-VTEMP2-Pad29)") (class "Default")
      (node (ref "U$6") (pin "29") (pinfunction "VTEMP2_29") (pintype "bidirectional"))
    )
  )
)
